# base.net
KiCad netlist of a schematic drawn in Altium Designer
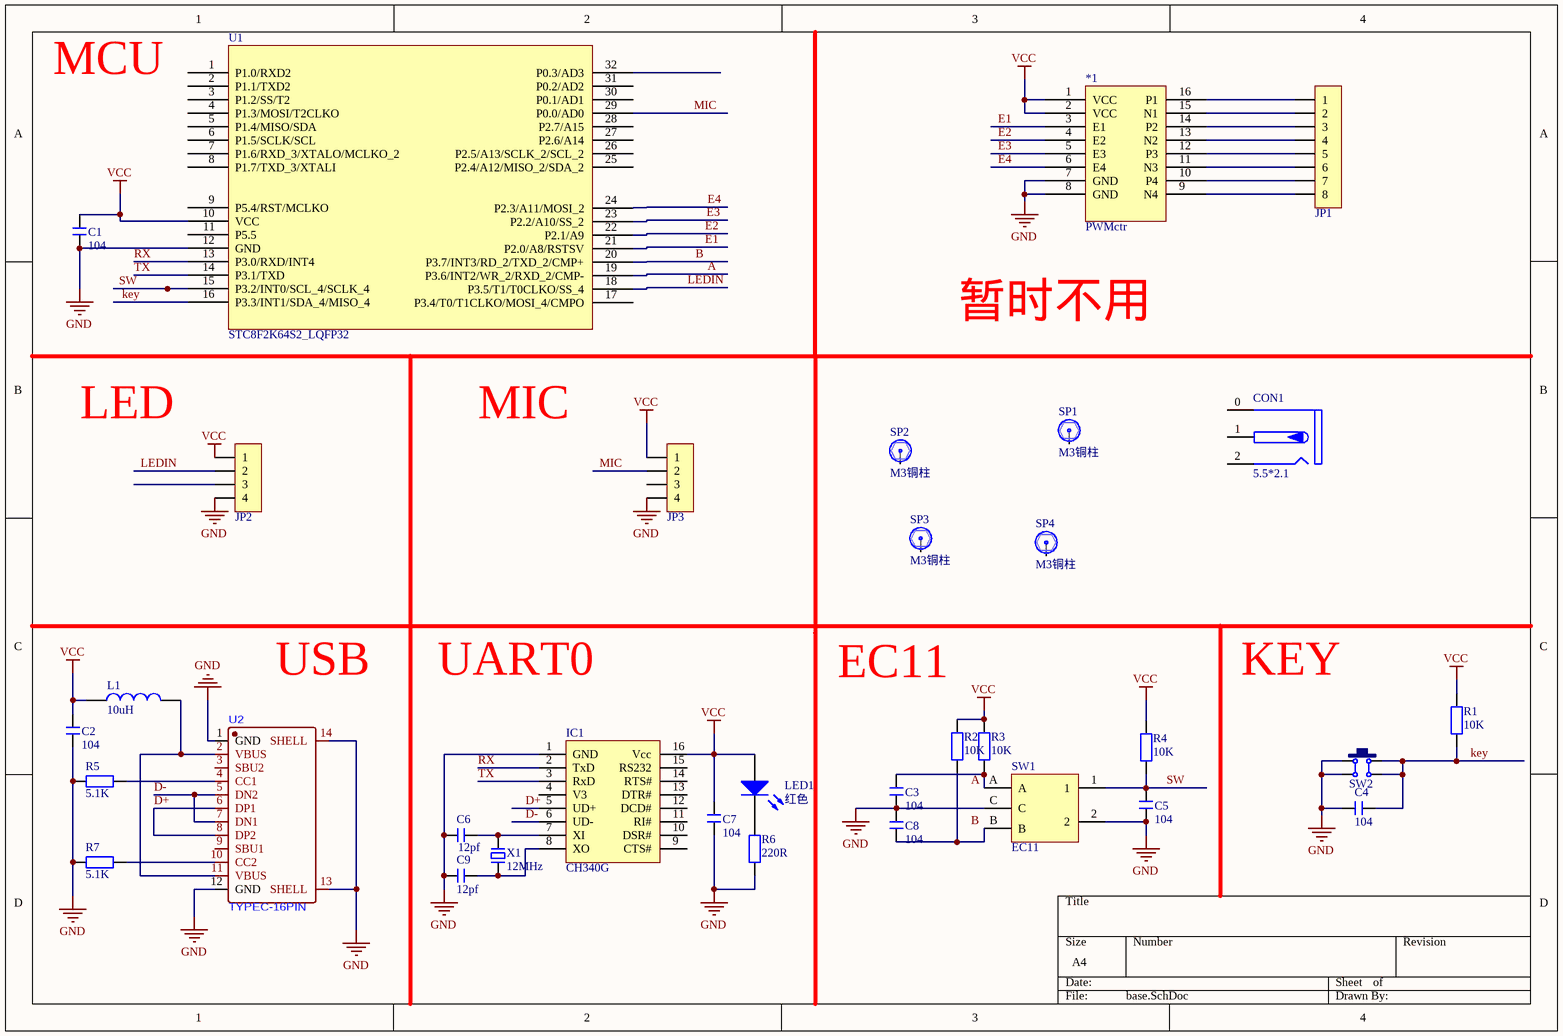
[diagram p0: base.SchDoc]

(export (version "E")
  (design (tool "Eeschema 10.0.6"))
  (components
    (comp (ref "*1")
      (value "PWMctr")
      (footprint "PWMctr")
      (description "PWM控制板")
      (libsource (lib "模块") (part "PWMctr"))
    )
    (comp (ref "C1")
      (value "104")
      (footprint "C 0805_L")
      (description "贴片电容")
      (libsource (lib "0.1 - 电阻-电容-电感") (part "C"))
    )
    (comp (ref "C2")
      (value "104")
      (footprint "C 0805_L")
      (description "贴片电容")
      (libsource (lib "0.1 - 电阻-电容-电感") (part "C"))
    )
    (comp (ref "C3")
      (value "104")
      (footprint "C 0805_L")
      (description "贴片电容")
      (libsource (lib "0.1 - 电阻-电容-电感") (part "C"))
    )
    (comp (ref "C4")
      (value "104")
      (footprint "C 0805_L")
      (description "贴片电容")
      (libsource (lib "0.1 - 电阻-电容-电感") (part "C"))
    )
    (comp (ref "C5")
      (value "104")
      (footprint "C 0805_L")
      (description "贴片电容")
      (libsource (lib "0.1 - 电阻-电容-电感") (part "C"))
    )
    (comp (ref "C6")
      (value "12pf")
      (footprint "C 0805_L")
      (description "贴片电容")
      (libsource (lib "0.1 - 电阻-电容-电感") (part "C"))
    )
    (comp (ref "C7")
      (value "104")
      (footprint "C 0805_L")
      (description "贴片电容")
      (libsource (lib "0.1 - 电阻-电容-电感") (part "C"))
    )
    (comp (ref "C8")
      (value "104")
      (footprint "C 0805_L")
      (description "贴片电容")
      (libsource (lib "0.1 - 电阻-电容-电感") (part "C"))
    )
    (comp (ref "C9")
      (value "12pf")
      (footprint "C 0805_L")
      (description "贴片电容")
      (libsource (lib "0.1 - 电阻-电容-电感") (part "C"))
    )
    (comp (ref "CON1")
      (value "5.5*2.1")
      (footprint "DC-005P")
      (description "带屏蔽DC电源接口")
      (libsource (lib "0.8 - 以太网-音频-USB插座") (part "DC-005P"))
    )
    (comp (ref "IC1")
      (value "CH340G")
      (footprint "SOP16_L")
      (description "串口转USB")
      (fields (field (name "版权归属") "封装库来自淘宝 ID：黄晶宝石"))
      (libsource (lib "1.0 - 常见芯片") (part "CH340G"))
    )
    (comp (ref "JP1")
      (value "HDR-1X8")
      (footprint "XH2.54-WI-8P")
      (description "8P接插件")
      (fields (field (name "版权归属") "封装库来自淘宝 ID：黄晶宝石"))
      (libsource (lib "5.3 - 接插件-脚距2.54 (100mil) ") (part "Header 8"))
    )
    (comp (ref "JP2")
      (value "HDR-1X4")
      (footprint "XH2.54-WI-4P")
      (description "4P接插件")
      (fields (field (name "版权归属") "封装库来自淘宝 ID：黄晶宝石"))
      (libsource (lib "5.3 - 接插件-脚距2.54 (100mil) ") (part "Header 4"))
    )
    (comp (ref "JP3")
      (value "HDR-1X4")
      (footprint "XH2.54-WI-4P")
      (description "4P接插件")
      (fields (field (name "版权归属") "封装库来自淘宝 ID：黄晶宝石"))
      (libsource (lib "5.3 - 接插件-脚距2.54 (100mil) ") (part "Header 4"))
    )
    (comp (ref "L1")
      (value "10uH")
      (footprint "L 1206")
      (description "小功率贴片电感")
      (libsource (lib "0.1 - 电阻-电容-电感") (part "L"))
    )
    (comp (ref "LED1")
      (value "红色")
      (footprint "LED 3MM-B")
      (description "直插3mm LED")
      (fields (field (name "版权归属") "封装库来自淘宝 ID：黄晶宝石"))
      (libsource (lib "0.3 - LED发光二极管") (part "LED-3MM"))
    )
    (comp (ref "R1")
      (value "10K")
      (footprint "R 0805_L")
      (description "贴片电阻")
      (fields (field (name "版权归属") "来自淘宝 ID：黄晶宝石"))
      (libsource (lib "0.1 - 电阻-电容-电感") (part "R"))
    )
    (comp (ref "R2")
      (value "10K")
      (footprint "R 0805_L")
      (description "贴片电阻")
      (fields (field (name "版权归属") "来自淘宝 ID：黄晶宝石"))
      (libsource (lib "0.1 - 电阻-电容-电感") (part "R"))
    )
    (comp (ref "R3")
      (value "10K")
      (footprint "R 0805_L")
      (description "贴片电阻")
      (fields (field (name "版权归属") "来自淘宝 ID：黄晶宝石"))
      (libsource (lib "0.1 - 电阻-电容-电感") (part "R"))
    )
    (comp (ref "R4")
      (value "10K")
      (footprint "R 0805_L")
      (description "贴片电阻")
      (fields (field (name "版权归属") "来自淘宝 ID：黄晶宝石"))
      (libsource (lib "0.1 - 电阻-电容-电感") (part "R"))
    )
    (comp (ref "R5")
      (value "5.1K")
      (footprint "R 0805_L")
      (description "贴片电阻")
      (fields (field (name "版权归属") "来自淘宝 ID：黄晶宝石"))
      (libsource (lib "0.1 - 电阻-电容-电感") (part "R"))
    )
    (comp (ref "R6")
      (value "220R")
      (footprint "R 0805_L")
      (description "贴片电阻")
      (fields (field (name "版权归属") "来自淘宝 ID：黄晶宝石"))
      (libsource (lib "0.1 - 电阻-电容-电感") (part "R"))
    )
    (comp (ref "R7")
      (value "5.1K")
      (footprint "R 0805_L")
      (description "贴片电阻")
      (fields (field (name "版权归属") "来自淘宝 ID：黄晶宝石"))
      (libsource (lib "0.1 - 电阻-电容-电感") (part "R"))
    )
    (comp (ref "SP1")
      (value "M3铜柱")
      (footprint "M3x4+6_N")
      (description "铜柱")
      (fields (field (name "版权归属") "封装库来自淘宝 ID：黄晶宝石"))
      (libsource (lib "4.1 - 未分类器件") (part "铜柱加头大焊盘"))
    )
    (comp (ref "SP2")
      (value "M3铜柱")
      (footprint "M3x4+6_N")
      (description "铜柱")
      (fields (field (name "版权归属") "封装库来自淘宝 ID：黄晶宝石"))
      (libsource (lib "4.1 - 未分类器件") (part "铜柱加头大焊盘"))
    )
    (comp (ref "SP3")
      (value "M3铜柱")
      (footprint "M3x4+6_N")
      (description "铜柱")
      (fields (field (name "版权归属") "封装库来自淘宝 ID：黄晶宝石"))
      (libsource (lib "4.1 - 未分类器件") (part "铜柱加头大焊盘"))
    )
    (comp (ref "SP4")
      (value "M3铜柱")
      (footprint "M3x4+6_N")
      (description "铜柱")
      (fields (field (name "版权归属") "封装库来自淘宝 ID：黄晶宝石"))
      (libsource (lib "4.1 - 未分类器件") (part "铜柱加头大焊盘"))
    )
    (comp (ref "SW1")
      (value "EC11")
      (footprint "EC11")
      (description "数字开关编码器")
      (fields (field (name "版权归属") "封装库来自淘宝 ID：黄晶宝石"))
      (libsource (lib "0.7 - 常用按键-开关") (part "EC11"))
    )
    (comp (ref "SW2")
      (value "12x12x5")
      (footprint "TSW DIP-12*12*12")
      (description "直插12x12轻触开关")
      (fields (field (name "版权归属") "封装库来自淘宝 ID：黄晶宝石"))
      (libsource (lib "0.7 - 常用按键-开关") (part "TSW DIP-12x12"))
    )
    (comp (ref "U1") (value "STC8F2K64S2_LQFP32") (footprint "MCU") (libsource (lib "模块") (part "MCU")))
    (comp (ref "U2")
      (value "TYPEC-16PIN")
      (footprint "USB-C-16pin")
      (libsource (lib "usb") (part "TYPEC-16PIN"))
    )
    (comp (ref "X1")
      (value "12MHz")
      (footprint "OSC HC-49S")
      (description "2脚无源脚晶振")
      (fields (field (name "版权归属") "封装库来自淘宝卖家 ID：黄晶宝石"))
      (libsource (lib "2.0 - 保险丝-晶振-光耦") (part "XTAL-2P"))
    )
  )
  (nets
    (net (code "1") (name "/A") (class "Default")
      (node (ref "U1") (pin "19") (pinfunction "P3.6/INT2/WR_2/RXD_2/CMP-_19") (pintype "passive"))
    )
    (net (code "2") (name "/B") (class "Default")
      (node (ref "U1") (pin "20") (pinfunction "P3.7/INT3/RD_2/TXD_2/CMP+_20") (pintype "passive"))
    )
    (net (code "3") (name "/D+") (class "Default")
      (node (ref "IC1") (pin "5") (pinfunction "UD+_5") (pintype "passive"))
      (node (ref "U2") (pin "6") (pinfunction "DP1_6") (pintype "passive"))
      (node (ref "U2") (pin "8") (pinfunction "DP2_8") (pintype "passive"))
    )
    (net (code "4") (name "/D-") (class "Default")
      (node (ref "IC1") (pin "6") (pinfunction "UD-_6") (pintype "passive"))
      (node (ref "U2") (pin "5") (pinfunction "DN2_5") (pintype "passive"))
      (node (ref "U2") (pin "7") (pinfunction "DN1_7") (pintype "passive"))
    )
    (net (code "5") (name "/E1") (class "Default")
      (node (ref "*1") (pin "3") (pinfunction "E1_3") (pintype "passive"))
      (node (ref "U1") (pin "21") (pinfunction "P2.0/A8/RSTSV_21") (pintype "passive"))
    )
    (net (code "6") (name "/E2") (class "Default")
      (node (ref "*1") (pin "4") (pinfunction "E2_4") (pintype "passive"))
      (node (ref "U1") (pin "22") (pinfunction "P2.1/A9_22") (pintype "passive"))
    )
    (net (code "7") (name "/E3") (class "Default")
      (node (ref "*1") (pin "5") (pinfunction "E3_5") (pintype "passive"))
      (node (ref "U1") (pin "23") (pinfunction "P2.2/A10/SS_2_23") (pintype "passive"))
    )
    (net (code "8") (name "/E4") (class "Default")
      (node (ref "*1") (pin "6") (pinfunction "E4_6") (pintype "passive"))
      (node (ref "U1") (pin "24") (pinfunction "P2.3/A11/MOSI_2_24") (pintype "passive"))
    )
    (net (code "9") (name "/LEDIN") (class "Default")
      (node (ref "JP2") (pin "2") (pinfunction "2_2") (pintype "passive"))
      (node (ref "U1") (pin "18") (pinfunction "P3.5/T1/T0CLKO/SS_4_18") (pintype "passive"))
    )
    (net (code "10") (name "/MIC") (class "Default")
      (node (ref "JP3") (pin "2") (pinfunction "2_2") (pintype "passive"))
      (node (ref "U1") (pin "29") (pinfunction "P0.0/AD0_29") (pintype "passive"))
    )
    (net (code "11") (name "/RX") (class "Default")
      (node (ref "IC1") (pin "2") (pinfunction "TxD_2") (pintype "passive"))
      (node (ref "U1") (pin "13") (pinfunction "P3.0/RXD/INT4_13") (pintype "passive"))
    )
    (net (code "12") (name "/SW") (class "Default")
      (node (ref "C5") (pin "1") (pinfunction "1_1") (pintype "passive"))
      (node (ref "R4") (pin "2") (pinfunction "2_2") (pintype "passive"))
      (node (ref "SW1") (pin "1") (pinfunction "1_1") (pintype "passive"))
      (node (ref "U1") (pin "15") (pinfunction "P3.2/INT0/SCL_4/SCLK_4_15") (pintype "passive"))
    )
    (net (code "13") (name "/TX") (class "Default")
      (node (ref "IC1") (pin "3") (pinfunction "RxD_3") (pintype "passive"))
      (node (ref "U1") (pin "14") (pinfunction "P3.1/TXD_14") (pintype "passive"))
    )
    (net (code "14") (name "/key") (class "Default")
      (node (ref "C4") (pin "2") (pinfunction "2_2") (pintype "passive"))
      (node (ref "R1") (pin "2") (pinfunction "2_2") (pintype "passive"))
      (node (ref "SW2") (pin "2") (pinfunction "2_2") (pintype "passive"))
      (node (ref "SW2") (pin "3") (pinfunction "3_3") (pintype "passive"))
      (node (ref "U1") (pin "16") (pinfunction "P3.3/INT1/SDA_4/MISO_4_16") (pintype "passive"))
    )
    (net (code "15") (name "GND") (class "Default")
      (node (ref "*1") (pin "7") (pinfunction "GND_7") (pintype "passive"))
      (node (ref "*1") (pin "8") (pinfunction "GND_8") (pintype "passive"))
      (node (ref "C1") (pin "1") (pinfunction "1_1") (pintype "passive"))
      (node (ref "C2") (pin "1") (pinfunction "1_1") (pintype "passive"))
      (node (ref "C3") (pin "2") (pinfunction "2_2") (pintype "passive"))
      (node (ref "C4") (pin "1") (pinfunction "1_1") (pintype "passive"))
      (node (ref "C5") (pin "2") (pinfunction "2_2") (pintype "passive"))
      (node (ref "C6") (pin "2") (pinfunction "2_2") (pintype "passive"))
      (node (ref "C7") (pin "2") (pinfunction "2_2") (pintype "passive"))
      (node (ref "C8") (pin "1") (pinfunction "1_1") (pintype "passive"))
      (node (ref "C9") (pin "2") (pinfunction "2_2") (pintype "passive"))
      (node (ref "IC1") (pin "1") (pinfunction "GND_1") (pintype "passive"))
      (node (ref "JP2") (pin "4") (pinfunction "4_4") (pintype "passive"))
      (node (ref "JP3") (pin "4") (pinfunction "4_4") (pintype "passive"))
      (node (ref "R5") (pin "2") (pinfunction "2_2") (pintype "passive"))
      (node (ref "R6") (pin "2") (pinfunction "2_2") (pintype "passive"))
      (node (ref "R7") (pin "2") (pinfunction "2_2") (pintype "passive"))
      (node (ref "SW1") (pin "2") (pinfunction "2_2") (pintype "passive"))
      (node (ref "SW1") (pin "C") (pinfunction "C_C") (pintype "passive"))
      (node (ref "SW2") (pin "1") (pinfunction "1_1") (pintype "passive"))
      (node (ref "SW2") (pin "4") (pinfunction "4_4") (pintype "passive"))
      (node (ref "U1") (pin "12") (pinfunction "GND_12") (pintype "passive"))
      (node (ref "U2") (pin "1") (pinfunction "GND_1") (pintype "passive"))
      (node (ref "U2") (pin "12") (pinfunction "GND_12") (pintype "passive"))
      (node (ref "U2") (pin "13") (pinfunction "SHELL_13") (pintype "passive"))
      (node (ref "U2") (pin "14") (pinfunction "SHELL_14") (pintype "passive"))
    )
    (net (code "16") (name "Net-(*1-N1)") (class "Default")
      (node (ref "*1") (pin "15") (pinfunction "N1_15") (pintype "passive"))
      (node (ref "JP1") (pin "2") (pinfunction "2_2") (pintype "passive"))
    )
    (net (code "17") (name "Net-(*1-N2)") (class "Default")
      (node (ref "*1") (pin "13") (pinfunction "N2_13") (pintype "passive"))
      (node (ref "JP1") (pin "4") (pinfunction "4_4") (pintype "passive"))
    )
    (net (code "18") (name "Net-(*1-N3)") (class "Default")
      (node (ref "*1") (pin "11") (pinfunction "N3_11") (pintype "passive"))
      (node (ref "JP1") (pin "6") (pinfunction "6_6") (pintype "passive"))
    )
    (net (code "19") (name "Net-(*1-N4)") (class "Default")
      (node (ref "*1") (pin "9") (pinfunction "N4_9") (pintype "passive"))
      (node (ref "JP1") (pin "8") (pinfunction "8_8") (pintype "passive"))
    )
    (net (code "20") (name "Net-(*1-P1)") (class "Default")
      (node (ref "*1") (pin "16") (pinfunction "P1_16") (pintype "passive"))
      (node (ref "JP1") (pin "1") (pinfunction "1_1") (pintype "passive"))
    )
    (net (code "21") (name "Net-(*1-P2)") (class "Default")
      (node (ref "*1") (pin "14") (pinfunction "P2_14") (pintype "passive"))
      (node (ref "JP1") (pin "3") (pinfunction "3_3") (pintype "passive"))
    )
    (net (code "22") (name "Net-(*1-P3)") (class "Default")
      (node (ref "*1") (pin "12") (pinfunction "P3_12") (pintype "passive"))
      (node (ref "JP1") (pin "5") (pinfunction "5_5") (pintype "passive"))
    )
    (net (code "23") (name "Net-(*1-P4)") (class "Default")
      (node (ref "*1") (pin "10") (pinfunction "P4_10") (pintype "passive"))
      (node (ref "JP1") (pin "7") (pinfunction "7_7") (pintype "passive"))
    )
    (net (code "24") (name "Net-(C3-Pad1)") (class "Default")
      (node (ref "C3") (pin "1") (pinfunction "1_1") (pintype "passive"))
      (node (ref "R3") (pin "2") (pinfunction "2_2") (pintype "passive"))
      (node (ref "SW1") (pin "A") (pinfunction "A_A") (pintype "passive"))
    )
    (net (code "25") (name "Net-(C8-Pad2)") (class "Default")
      (node (ref "C8") (pin "2") (pinfunction "2_2") (pintype "passive"))
      (node (ref "R2") (pin "2") (pinfunction "2_2") (pintype "passive"))
      (node (ref "SW1") (pin "B") (pinfunction "B_B") (pintype "passive"))
    )
    (net (code "26") (name "Net-(IC1-XI)") (class "Default")
      (node (ref "C6") (pin "1") (pinfunction "1_1") (pintype "passive"))
      (node (ref "IC1") (pin "7") (pinfunction "XI_7") (pintype "passive"))
      (node (ref "X1") (pin "1") (pinfunction "1_1") (pintype "passive"))
    )
    (net (code "27") (name "Net-(IC1-XO)") (class "Default")
      (node (ref "C9") (pin "1") (pinfunction "1_1") (pintype "passive"))
      (node (ref "IC1") (pin "8") (pinfunction "XO_8") (pintype "passive"))
      (node (ref "X1") (pin "2") (pinfunction "2_2") (pintype "passive"))
    )
    (net (code "28") (name "Net-(L1-Pad2)") (class "Default")
      (node (ref "L1") (pin "2") (pinfunction "2_2") (pintype "passive"))
      (node (ref "U2") (pin "11") (pinfunction "VBUS_11") (pintype "passive"))
      (node (ref "U2") (pin "2") (pinfunction "VBUS_2") (pintype "passive"))
    )
    (net (code "29") (name "Net-(LED1-K)") (class "Default")
      (node (ref "LED1") (pin "2") (pinfunction "K_2") (pintype "passive"))
      (node (ref "R6") (pin "1") (pinfunction "1_1") (pintype "passive"))
    )
    (net (code "30") (name "Net-(U2-CC1)") (class "Default")
      (node (ref "R5") (pin "1") (pinfunction "1_1") (pintype "passive"))
      (node (ref "U2") (pin "4") (pinfunction "CC1_4") (pintype "passive"))
    )
    (net (code "31") (name "Net-(U2-CC2)") (class "Default")
      (node (ref "R7") (pin "1") (pinfunction "1_1") (pintype "passive"))
      (node (ref "U2") (pin "10") (pinfunction "CC2_10") (pintype "passive"))
    )
    (net (code "32") (name "VCC") (class "Default")
      (node (ref "*1") (pin "1") (pinfunction "VCC_1") (pintype "passive"))
      (node (ref "*1") (pin "2") (pinfunction "VCC_2") (pintype "passive"))
      (node (ref "C1") (pin "2") (pinfunction "2_2") (pintype "passive"))
      (node (ref "C2") (pin "2") (pinfunction "2_2") (pintype "passive"))
      (node (ref "C7") (pin "1") (pinfunction "1_1") (pintype "passive"))
      (node (ref "IC1") (pin "16") (pinfunction "Vcc_16") (pintype "passive"))
      (node (ref "JP2") (pin "1") (pinfunction "1_1") (pintype "passive"))
      (node (ref "JP3") (pin "1") (pinfunction "1_1") (pintype "passive"))
      (node (ref "L1") (pin "1") (pinfunction "1_1") (pintype "passive"))
      (node (ref "LED1") (pin "1") (pinfunction "A_1") (pintype "passive"))
      (node (ref "R1") (pin "1") (pinfunction "1_1") (pintype "passive"))
      (node (ref "R2") (pin "1") (pinfunction "1_1") (pintype "passive"))
      (node (ref "R3") (pin "1") (pinfunction "1_1") (pintype "passive"))
      (node (ref "R4") (pin "1") (pinfunction "1_1") (pintype "passive"))
      (node (ref "U1") (pin "10") (pinfunction "VCC_10") (pintype "passive"))
    )
    (net (code "33") (name "unconnected-(CON1-Pad0)") (class "Default")
      (node (ref "CON1") (pin "0") (pintype "power_in"))
    )
    (net (code "34") (name "unconnected-(CON1-Pad1)") (class "Default")
      (node (ref "CON1") (pin "1") (pintype "power_in"))
    )
    (net (code "35") (name "unconnected-(CON1-Pad2)") (class "Default")
      (node (ref "CON1") (pin "2") (pintype "power_in"))
    )
    (net (code "36") (name "unconnected-(IC1-CTS#-Pad9)") (class "Default")
      (node (ref "IC1") (pin "9") (pinfunction "CTS#_9") (pintype "passive"))
    )
    (net (code "37") (name "unconnected-(IC1-DCD#-Pad12)") (class "Default")
      (node (ref "IC1") (pin "12") (pinfunction "DCD#_12") (pintype "passive"))
    )
    (net (code "38") (name "unconnected-(IC1-DSR#-Pad10)") (class "Default")
      (node (ref "IC1") (pin "10") (pinfunction "DSR#_10") (pintype "passive"))
    )
    (net (code "39") (name "unconnected-(IC1-DTR#-Pad13)") (class "Default")
      (node (ref "IC1") (pin "13") (pinfunction "DTR#_13") (pintype "passive"))
    )
    (net (code "40") (name "unconnected-(IC1-RI#-Pad11)") (class "Default")
      (node (ref "IC1") (pin "11") (pinfunction "RI#_11") (pintype "passive"))
    )
    (net (code "41") (name "unconnected-(IC1-RS232-Pad15)") (class "Default")
      (node (ref "IC1") (pin "15") (pinfunction "RS232_15") (pintype "passive"))
    )
    (net (code "42") (name "unconnected-(IC1-RTS#-Pad14)") (class "Default")
      (node (ref "IC1") (pin "14") (pinfunction "RTS#_14") (pintype "passive"))
    )
    (net (code "43") (name "unconnected-(IC1-V3-Pad4)") (class "Default")
      (node (ref "IC1") (pin "4") (pinfunction "V3_4") (pintype "passive"))
    )
    (net (code "44") (name "unconnected-(JP2-Pad3)") (class "Default")
      (node (ref "JP2") (pin "3") (pinfunction "3_3") (pintype "passive"))
    )
    (net (code "45") (name "unconnected-(JP3-Pad3)") (class "Default")
      (node (ref "JP3") (pin "3") (pinfunction "3_3") (pintype "passive"))
    )
    (net (code "46") (name "unconnected-(SP1-Pad1)") (class "Default")
      (node (ref "SP1") (pin "1") (pinfunction "1_1") (pintype "passive"))
    )
    (net (code "47") (name "unconnected-(SP2-Pad1)") (class "Default")
      (node (ref "SP2") (pin "1") (pinfunction "1_1") (pintype "passive"))
    )
    (net (code "48") (name "unconnected-(SP3-Pad1)") (class "Default")
      (node (ref "SP3") (pin "1") (pinfunction "1_1") (pintype "passive"))
    )
    (net (code "49") (name "unconnected-(SP4-Pad1)") (class "Default")
      (node (ref "SP4") (pin "1") (pinfunction "1_1") (pintype "passive"))
    )
    (net (code "50") (name "unconnected-(U1-P0.1{slash}AD1-Pad30)") (class "Default")
      (node (ref "U1") (pin "30") (pinfunction "P0.1/AD1_30") (pintype "passive"))
    )
    (net (code "51") (name "unconnected-(U1-P0.2{slash}AD2-Pad31)") (class "Default")
      (node (ref "U1") (pin "31") (pinfunction "P0.2/AD2_31") (pintype "passive"))
    )
    (net (code "52") (name "unconnected-(U1-P0.3{slash}AD3-Pad32)") (class "Default")
      (node (ref "U1") (pin "32") (pinfunction "P0.3/AD3_32") (pintype "passive"))
    )
    (net (code "53") (name "unconnected-(U1-P1.0{slash}RXD2-Pad1)") (class "Default")
      (node (ref "U1") (pin "1") (pinfunction "P1.0/RXD2_1") (pintype "passive"))
    )
    (net (code "54") (name "unconnected-(U1-P1.1{slash}TXD2-Pad2)") (class "Default")
      (node (ref "U1") (pin "2") (pinfunction "P1.1/TXD2_2") (pintype "passive"))
    )
    (net (code "55") (name "unconnected-(U1-P1.2{slash}SS{slash}T2-Pad3)") (class "Default")
      (node (ref "U1") (pin "3") (pinfunction "P1.2/SS/T2_3") (pintype "passive"))
    )
    (net (code "56") (name "unconnected-(U1-P1.3{slash}MOSI{slash}T2CLKO-Pad4)") (class "Default")
      (node (ref "U1") (pin "4") (pinfunction "P1.3/MOSI/T2CLKO_4") (pintype "passive"))
    )
    (net (code "57") (name "unconnected-(U1-P1.4{slash}MISO{slash}SDA-Pad5)") (class "Default")
      (node (ref "U1") (pin "5") (pinfunction "P1.4/MISO/SDA_5") (pintype "passive"))
    )
    (net (code "58") (name "unconnected-(U1-P1.5{slash}SCLK{slash}SCL-Pad6)") (class "Default")
      (node (ref "U1") (pin "6") (pinfunction "P1.5/SCLK/SCL_6") (pintype "passive"))
    )
    (net (code "59") (name "unconnected-(U1-P1.6{slash}RXD_3{slash}XTALO{slash}MCLKO_2-Pad7)") (class "Default")
      (node (ref "U1") (pin "7") (pinfunction "P1.6/RXD_3/XTALO/MCLKO_2_7") (pintype "passive"))
    )
    (net (code "60") (name "unconnected-(U1-P1.7{slash}TXD_3{slash}XTALI-Pad8)") (class "Default")
      (node (ref "U1") (pin "8") (pinfunction "P1.7/TXD_3/XTALI_8") (pintype "passive"))
    )
    (net (code "61") (name "unconnected-(U1-P2.4{slash}A12{slash}MISO_2{slash}SDA_2-Pad25)") (class "Default")
      (node (ref "U1") (pin "25") (pinfunction "P2.4/A12/MISO_2/SDA_2_25") (pintype "passive"))
    )
    (net (code "62") (name "unconnected-(U1-P2.5{slash}A13{slash}SCLK_2{slash}SCL_2-Pad26)") (class "Default")
      (node (ref "U1") (pin "26") (pinfunction "P2.5/A13/SCLK_2/SCL_2_26") (pintype "passive"))
    )
    (net (code "63") (name "unconnected-(U1-P2.6{slash}A14-Pad27)") (class "Default")
      (node (ref "U1") (pin "27") (pinfunction "P2.6/A14_27") (pintype "passive"))
    )
    (net (code "64") (name "unconnected-(U1-P2.7{slash}A15-Pad28)") (class "Default")
      (node (ref "U1") (pin "28") (pinfunction "P2.7/A15_28") (pintype "passive"))
    )
    (net (code "65") (name "unconnected-(U1-P3.4{slash}T0{slash}T1CLKO{slash}MOSI_4{slash}CMPO-Pad17)") (class "Default")
      (node (ref "U1") (pin "17") (pinfunction "P3.4/T0/T1CLKO/MOSI_4/CMPO_17") (pintype "passive"))
    )
    (net (code "66") (name "unconnected-(U1-P5.4{slash}RST{slash}MCLKO-Pad9)") (class "Default")
      (node (ref "U1") (pin "9") (pinfunction "P5.4/RST/MCLKO_9") (pintype "passive"))
    )
    (net (code "67") (name "unconnected-(U1-P5.5-Pad11)") (class "Default")
      (node (ref "U1") (pin "11") (pinfunction "P5.5_11") (pintype "passive"))
    )
    (net (code "68") (name "unconnected-(U2-SBU1-Pad9)") (class "Default")
      (node (ref "U2") (pin "9") (pinfunction "SBU1_9") (pintype "passive"))
    )
    (net (code "69") (name "unconnected-(U2-SBU2-Pad3)") (class "Default")
      (node (ref "U2") (pin "3") (pinfunction "SBU2_3") (pintype "passive"))
    )
  )
)
